# MotorDriver.net
KiCad netlist of a schematic drawn in Altium Designer
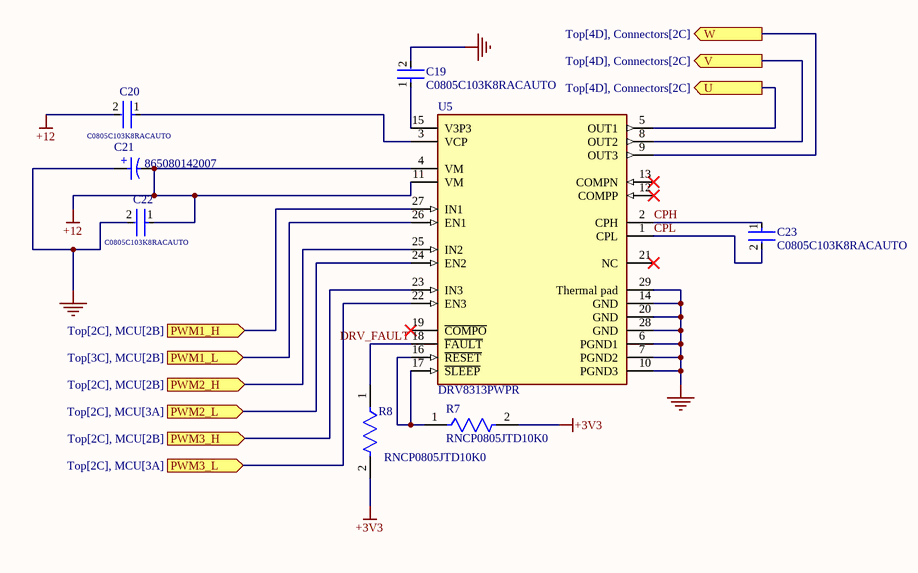
[diagram p0: MotorDriver.SchDoc]

(export (version "E")
  (design (tool "Eeschema 10.0.6"))
  (components
    (comp (ref "C19")
      (value "C0805C103K8RACAUTO")
      (footprint "FP-C0805C103K8RACAUTO-MFG")
      (description "C0805C103K8RACAUTO Cap, 0.01UF, 10V, Mlcc, 0805 Rohs Compliant: Yes")
      (fields (field (name "TOLERANCE") "10%"))
      (libsource (lib "Altium Content Vault") (part "b4654b650e69147ec39a6b967a45e02"))
    )
    (comp (ref "C20")
      (value "C0805C103K8RACAUTO")
      (footprint "FP-C0805C103K8RACAUTO-MFG")
      (description "C0805C103K8RACAUTO Cap, 0.01UF, 10V, Mlcc, 0805 Rohs Compliant: Yes")
      (fields (field (name "TOLERANCE") "10%"))
      (libsource (lib "Altium Content Vault") (part "b4654b650e69147ec39a6b967a45e02"))
    )
    (comp (ref "C21")
      (value "865080142007")
      (footprint "WCAP-ASLI_D5H5.5")
      (description "Alum. Electrolytic Cap 100UF 25V 5MMV-CHIP Wcap-asli, Lifetime 2000H +105OC")
      (fields (field (name "TOLERANCE") "20%"))
      (libsource (lib "Altium Content Vault") (part "Capacitor_Polarized"))
    )
    (comp (ref "C22")
      (value "C0805C103K8RACAUTO")
      (footprint "FP-C0805C103K8RACAUTO-MFG")
      (description "C0805C103K8RACAUTO Cap, 0.01UF, 10V, Mlcc, 0805 Rohs Compliant: Yes")
      (fields (field (name "TOLERANCE") "10%"))
      (libsource (lib "Altium Content Vault") (part "b4654b650e69147ec39a6b967a45e02"))
    )
    (comp (ref "C23")
      (value "C0805C103K8RACAUTO")
      (footprint "FP-C0805C103K8RACAUTO-MFG")
      (description "C0805C103K8RACAUTO Cap, 0.01UF, 10V, Mlcc, 0805 Rohs Compliant: Yes")
      (fields (field (name "TOLERANCE") "10%"))
      (libsource (lib "Altium Content Vault") (part "b4654b650e69147ec39a6b967a45e02"))
    )
    (comp (ref "R7")
      (value "RNCP0805JTD10K0")
      (footprint "FP-RNCP0805-IPC_B")
      (description "10kΩ ±5% 0.25W 0805 High Power Anti-Sulfur Thin Film Chip Resistor")
      (fields (field (name "TOLERANCE") "5%"))
      (libsource (lib "Altium Content Vault") (part "1029c3af85768c4190bb7ad29bc67b5"))
    )
    (comp (ref "R8")
      (value "RNCP0805JTD10K0")
      (footprint "FP-RNCP0805-IPC_B")
      (description "10kΩ ±5% 0.25W 0805 High Power Anti-Sulfur Thin Film Chip Resistor")
      (fields (field (name "TOLERANCE") "5%"))
      (libsource (lib "Altium Content Vault") (part "1029c3af85768c4190bb7ad29bc67b5"))
    )
    (comp (ref "U5")
      (value "DRV8313PWPR")
      (footprint "FP-PWP0028C-IPC_B")
      (description "IC MOTOR DRIVER 8V-60V 28HTSSOP")
      (libsource (lib "Altium Content Vault") (part "6c5e8d1d79df7918d4eb9ae5de6b4b8"))
    )
  )
  (nets
    (net (code "1") (name "+3V3") (class "Default")
      (node (ref "R7") (pin "2") (pinfunction "2_2") (pintype "passive"))
      (node (ref "R8") (pin "2") (pinfunction "2_2") (pintype "passive"))
    )
    (net (code "2") (name "+12") (class "Default")
      (node (ref "C20") (pin "2") (pinfunction "2_2") (pintype "passive"))
      (node (ref "C21") (pin "2") (pinfunction "N_2") (pintype "passive"))
      (node (ref "C22") (pin "1") (pinfunction "1_1") (pintype "passive"))
      (node (ref "U5") (pin "11") (pinfunction "VM_11") (pintype "power_in"))
      (node (ref "U5") (pin "4") (pinfunction "VM_4") (pintype "power_in"))
    )
    (net (code "3") (name "/CPH") (class "Default")
      (node (ref "C23") (pin "1") (pinfunction "1_1") (pintype "passive"))
      (node (ref "U5") (pin "2") (pinfunction "CPH_2") (pintype "power_in"))
    )
    (net (code "4") (name "/CPL") (class "Default")
      (node (ref "C23") (pin "2") (pinfunction "2_2") (pintype "passive"))
      (node (ref "U5") (pin "1") (pinfunction "CPL_1") (pintype "power_in"))
    )
    (net (code "5") (name "/DRV_FAULT") (class "Default")
      (node (ref "R8") (pin "1") (pinfunction "1_1") (pintype "passive"))
      (node (ref "U5") (pin "18") (pinfunction "~{FAULT}_18") (pintype "open_collector"))
    )
    (net (code "6") (name "/PWM1_H") (class "Default")
      (node (ref "U5") (pin "27") (pinfunction "IN1_27") (pintype "input"))
    )
    (net (code "7") (name "/PWM1_L") (class "Default")
      (node (ref "U5") (pin "26") (pinfunction "EN1_26") (pintype "input"))
    )
    (net (code "8") (name "/PWM2_H") (class "Default")
      (node (ref "U5") (pin "25") (pinfunction "IN2_25") (pintype "input"))
    )
    (net (code "9") (name "/PWM2_L") (class "Default")
      (node (ref "U5") (pin "24") (pinfunction "EN2_24") (pintype "input"))
    )
    (net (code "10") (name "/PWM3_H") (class "Default")
      (node (ref "U5") (pin "23") (pinfunction "IN3_23") (pintype "input"))
    )
    (net (code "11") (name "/PWM3_L") (class "Default")
      (node (ref "U5") (pin "22") (pinfunction "EN3_22") (pintype "input"))
    )
    (net (code "12") (name "/U") (class "Default")
      (node (ref "U5") (pin "5") (pinfunction "OUT1_5") (pintype "output"))
    )
    (net (code "13") (name "/V") (class "Default")
      (node (ref "U5") (pin "8") (pinfunction "OUT2_8") (pintype "output"))
    )
    (net (code "14") (name "/W") (class "Default")
      (node (ref "U5") (pin "9") (pinfunction "OUT3_9") (pintype "output"))
    )
    (net (code "15") (name "<NO NET>") (class "Default")
      (node (ref "C19") (pin "2") (pinfunction "2_2") (pintype "passive"))
      (node (ref "C21") (pin "1") (pinfunction "P_1") (pintype "passive"))
      (node (ref "C22") (pin "2") (pinfunction "2_2") (pintype "passive"))
      (node (ref "U5") (pin "10") (pinfunction "PGND3_10") (pintype "power_in"))
      (node (ref "U5") (pin "14") (pinfunction "GND_14") (pintype "power_in"))
      (node (ref "U5") (pin "20") (pinfunction "GND_20") (pintype "power_in"))
      (node (ref "U5") (pin "28") (pinfunction "GND_28") (pintype "power_in"))
      (node (ref "U5") (pin "29") (pinfunction "Thermal_pad_29") (pintype "power_in"))
      (node (ref "U5") (pin "6") (pinfunction "PGND1_6") (pintype "power_in"))
      (node (ref "U5") (pin "7") (pinfunction "PGND2_7") (pintype "power_in"))
    )
    (net (code "16") (name "Net-(U5-V3P3)") (class "Default")
      (node (ref "C19") (pin "1") (pinfunction "1_1") (pintype "passive"))
      (node (ref "U5") (pin "15") (pinfunction "V3P3_15") (pintype "power_in"))
    )
    (net (code "17") (name "Net-(U5-VCP)") (class "Default")
      (node (ref "C20") (pin "1") (pinfunction "1_1") (pintype "passive"))
      (node (ref "U5") (pin "3") (pinfunction "VCP_3") (pintype "power_in"))
    )
    (net (code "18") (name "Net-(U5-~{RESET})") (class "Default")
      (node (ref "R7") (pin "1") (pinfunction "1_1") (pintype "passive"))
      (node (ref "U5") (pin "16") (pinfunction "~{RESET}_16") (pintype "input"))
      (node (ref "U5") (pin "17") (pinfunction "~{SLEEP}_17") (pintype "input"))
    )
    (net (code "19") (name "unconnected-(U5-COMPN-Pad13)") (class "Default")
      (node (ref "U5") (pin "13") (pinfunction "COMPN_13") (pintype "input+no_connect"))
    )
    (net (code "20") (name "unconnected-(U5-COMPP-Pad12)") (class "Default")
      (node (ref "U5") (pin "12") (pinfunction "COMPP_12") (pintype "input+no_connect"))
    )
    (net (code "21") (name "unconnected-(U5-NC-Pad21)") (class "Default")
      (node (ref "U5") (pin "21") (pinfunction "NC_21") (pintype "passive+no_connect"))
    )
    (net (code "22") (name "unconnected-(U5-~{COMPO}-Pad19)") (class "Default")
      (node (ref "U5") (pin "19") (pinfunction "~{COMPO}_19") (pintype "open_collector+no_connect"))
    )
  )
)
